# Connectors.net
KiCad netlist of a schematic drawn in Altium Designer
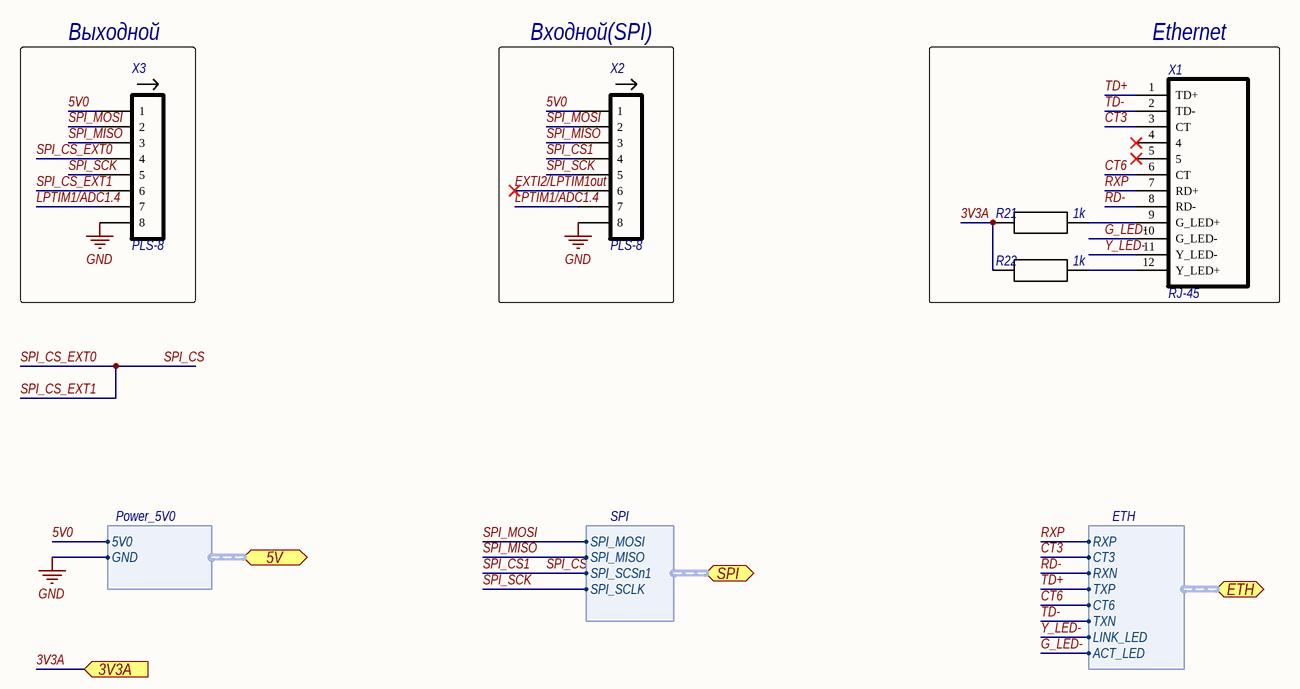
[diagram p0: Connectors.SchDoc]

(export (version "E")
  (design (tool "Eeschema 10.0.6"))
  (components
    (comp (ref "R21") (value "1k") (description "Resistor") (libsource (lib "Passive") (part "Resistor")))
    (comp (ref "R22") (value "1k") (description "Resistor") (libsource (lib "Passive") (part "Resistor")))
    (comp (ref "X1") (value "RJ-45") (libsource (lib "Connectors") (part "RJ-45")))
    (comp (ref "X2")
      (value "PLS-8")
      (footprint "B8B-PH-K-S(LF)(SN)")
      (libsource (lib "Connectors") (part "8-pin plug"))
    )
    (comp (ref "X3")
      (value "PLS-8")
      (footprint "B8B-PH-K-S(LF)(SN)")
      (libsource (lib "Connectors") (part "8-pin plug"))
    )
  )
  (nets
    (net (code "4") (name "/3V3A") (class "Default")
      (node (ref "R21") (pin "2") (pinfunction "2_2") (pintype "passive"))
      (node (ref "R22") (pin "2") (pinfunction "2_2") (pintype "passive"))
    )
    (net (code "5") (name "/5V0") (class "Default")
      (node (ref "X2") (pin "1") (pinfunction "1_1") (pintype "passive"))
      (node (ref "X3") (pin "1") (pinfunction "1_1") (pintype "passive"))
    )
    (net (code "6") (name "/CT3") (class "Default")
      (node (ref "X1") (pin "3") (pinfunction "CT_3") (pintype "passive"))
    )
    (net (code "7") (name "/CT6") (class "Default")
      (node (ref "X1") (pin "6") (pinfunction "CT_6") (pintype "passive"))
    )
    (net (code "8") (name "/EXTI2{slash}LPTIM1out") (class "Default")
      (node (ref "X2") (pin "6") (pinfunction "6_6") (pintype "passive+no_connect"))
    )
    (net (code "9") (name "/G_LED-") (class "Default")
      (node (ref "X1") (pin "10") (pinfunction "G_LED-_10") (pintype "passive"))
    )
    (net (code "10") (name "/LPTIM1{slash}ADC1.4") (class "Default")
      (node (ref "X2") (pin "7") (pinfunction "7_7") (pintype "passive"))
      (node (ref "X3") (pin "7") (pinfunction "7_7") (pintype "passive"))
    )
    (net (code "11") (name "/RD-") (class "Default")
      (node (ref "X1") (pin "8") (pinfunction "RD-_8") (pintype "passive"))
    )
    (net (code "12") (name "/RXP") (class "Default")
      (node (ref "X1") (pin "7") (pinfunction "RD+_7") (pintype "passive"))
    )
    (net (code "13") (name "/SPI_CS") (class "Default")
      (node (ref "X2") (pin "4") (pinfunction "4_4") (pintype "passive"))
      (node (ref "X3") (pin "4") (pinfunction "4_4") (pintype "passive"))
      (node (ref "X3") (pin "6") (pinfunction "6_6") (pintype "passive"))
    )
    (net (code "14") (name "/SPI_MISO") (class "Default")
      (node (ref "X2") (pin "3") (pinfunction "3_3") (pintype "passive"))
      (node (ref "X3") (pin "3") (pinfunction "3_3") (pintype "passive"))
    )
    (net (code "15") (name "/SPI_MOSI") (class "Default")
      (node (ref "X2") (pin "2") (pinfunction "2_2") (pintype "passive"))
      (node (ref "X3") (pin "2") (pinfunction "2_2") (pintype "passive"))
    )
    (net (code "16") (name "/SPI_SCK") (class "Default")
      (node (ref "X2") (pin "5") (pinfunction "5_5") (pintype "passive"))
      (node (ref "X3") (pin "5") (pinfunction "5_5") (pintype "passive"))
    )
    (net (code "17") (name "/TD+") (class "Default")
      (node (ref "X1") (pin "1") (pinfunction "TD+_1") (pintype "passive"))
    )
    (net (code "18") (name "/TD-") (class "Default")
      (node (ref "X1") (pin "2") (pinfunction "TD-_2") (pintype "passive"))
    )
    (net (code "19") (name "/Y_LED-") (class "Default")
      (node (ref "X1") (pin "11") (pinfunction "Y_LED-_11") (pintype "passive"))
    )
    (net (code "23") (name "GND") (class "Default")
      (node (ref "X2") (pin "8") (pinfunction "8_8") (pintype "passive"))
      (node (ref "X3") (pin "8") (pinfunction "8_8") (pintype "passive"))
    )
    (net (code "24") (name "Net-(X1-G_LED+)") (class "Default")
      (node (ref "R21") (pin "1") (pinfunction "1_1") (pintype "passive"))
      (node (ref "X1") (pin "9") (pinfunction "G_LED+_9") (pintype "passive"))
    )
    (net (code "25") (name "Net-(X1-Y_LED+)") (class "Default")
      (node (ref "R22") (pin "1") (pinfunction "1_1") (pintype "passive"))
      (node (ref "X1") (pin "12") (pinfunction "Y_LED+_12") (pintype "passive"))
    )
    (net (code "26") (name "unconnected-(X1-Pad4)") (class "Default")
      (node (ref "X1") (pin "4") (pinfunction "4_4") (pintype "passive+no_connect"))
    )
    (net (code "27") (name "unconnected-(X1-Pad5)") (class "Default")
      (node (ref "X1") (pin "5") (pinfunction "5_5") (pintype "passive+no_connect"))
    )
  )
)
